# RJ45_connector.net
KiCad netlist of a schematic drawn in EAGLE
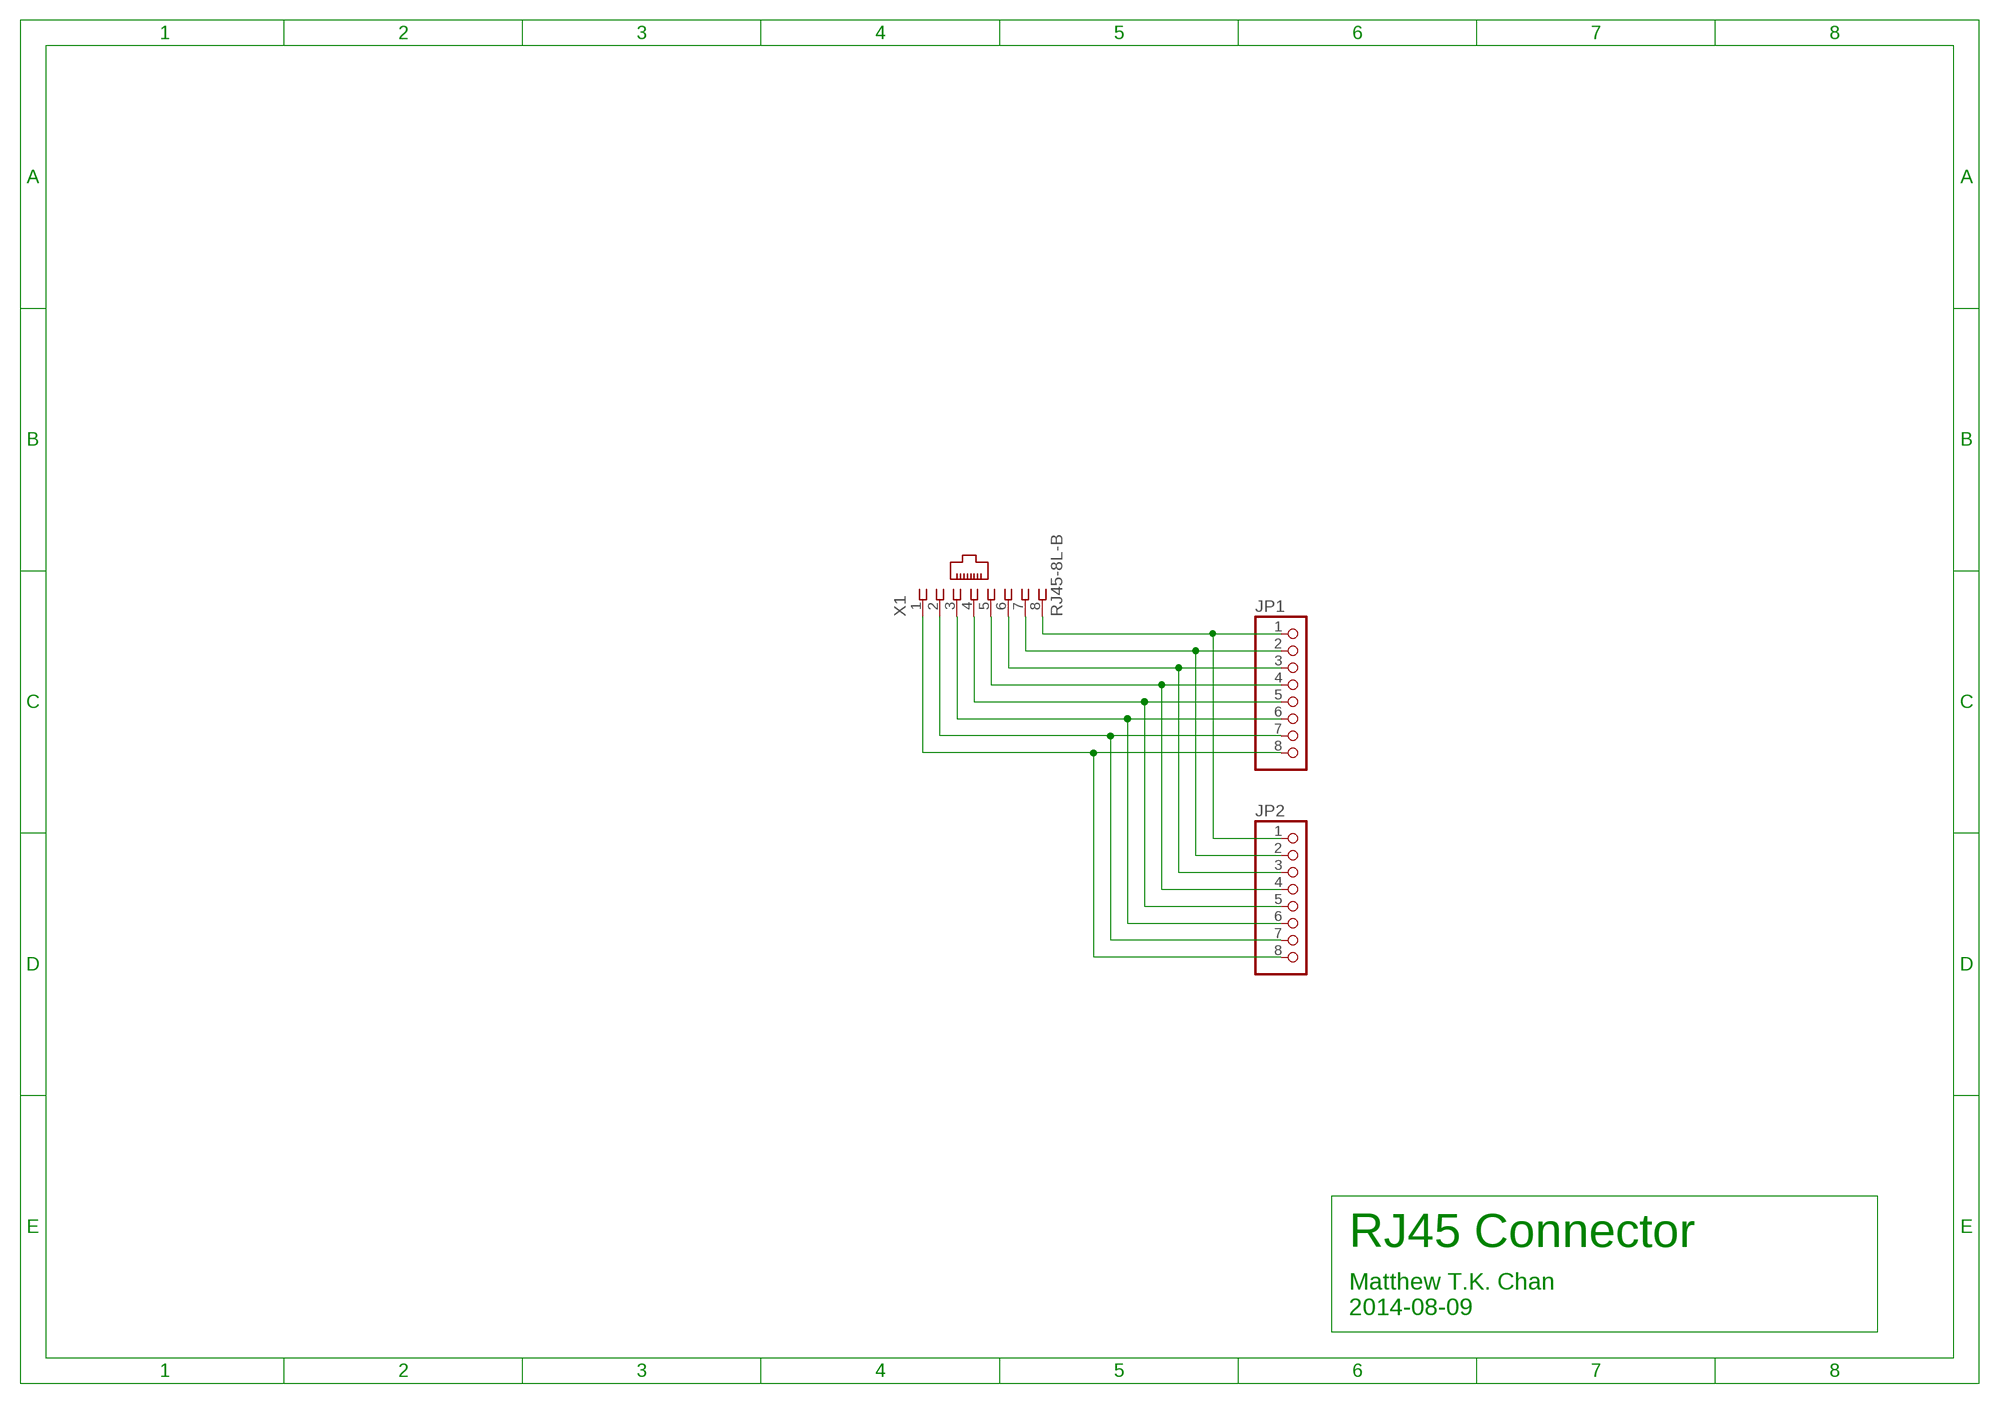
[diagram p0: schematic, sheet 1]

(export (version "E")
  (design (tool "Eeschema 10.0.6"))
  (components
    (comp (ref "JP1")
      (value "PINHD-1X8/90")
      (footprint "eagle-import:1X08_90")
      (libsource (lib "eagle-import") (part "PINHD-1X8/90"))
    )
    (comp (ref "JP2")
      (value "PINHD-1X8/90")
      (footprint "eagle-import:1X08_90")
      (libsource (lib "eagle-import") (part "PINHD-1X8/90"))
    )
    (comp (ref "X1")
      (value "RJ45-8L-B")
      (footprint "eagle-import:RJ45-NO-SHIELD")
      (fields (field (name "MF") "TYCO ELECTRONICS"))
      (libsource (lib "eagle-import") (part "RJ45-8L-B"))
    )
  )
  (nets
    (net (code "1") (name "Net-(JP1-Pad1)") (class "Default")
      (node (ref "JP1") (pin "1") (pinfunction "1_1") (pintype "passive"))
      (node (ref "JP2") (pin "1") (pinfunction "1_1") (pintype "passive"))
      (node (ref "X1") (pin "8") (pinfunction "8_8") (pintype "passive"))
    )
    (net (code "2") (name "Net-(JP1-Pad2)") (class "Default")
      (node (ref "JP1") (pin "2") (pinfunction "2_2") (pintype "passive"))
      (node (ref "JP2") (pin "2") (pinfunction "2_2") (pintype "passive"))
      (node (ref "X1") (pin "7") (pinfunction "7_7") (pintype "passive"))
    )
    (net (code "3") (name "Net-(JP1-Pad3)") (class "Default")
      (node (ref "JP1") (pin "3") (pinfunction "3_3") (pintype "passive"))
      (node (ref "JP2") (pin "3") (pinfunction "3_3") (pintype "passive"))
      (node (ref "X1") (pin "6") (pinfunction "6_6") (pintype "passive"))
    )
    (net (code "4") (name "Net-(JP1-Pad4)") (class "Default")
      (node (ref "JP1") (pin "4") (pinfunction "4_4") (pintype "passive"))
      (node (ref "JP2") (pin "4") (pinfunction "4_4") (pintype "passive"))
      (node (ref "X1") (pin "5") (pinfunction "5_5") (pintype "passive"))
    )
    (net (code "5") (name "Net-(JP1-Pad5)") (class "Default")
      (node (ref "JP1") (pin "5") (pinfunction "5_5") (pintype "passive"))
      (node (ref "JP2") (pin "5") (pinfunction "5_5") (pintype "passive"))
      (node (ref "X1") (pin "4") (pinfunction "4_4") (pintype "passive"))
    )
    (net (code "6") (name "Net-(JP1-Pad6)") (class "Default")
      (node (ref "JP1") (pin "6") (pinfunction "6_6") (pintype "passive"))
      (node (ref "JP2") (pin "6") (pinfunction "6_6") (pintype "passive"))
      (node (ref "X1") (pin "3") (pinfunction "3_3") (pintype "passive"))
    )
    (net (code "7") (name "Net-(JP1-Pad7)") (class "Default")
      (node (ref "JP1") (pin "7") (pinfunction "7_7") (pintype "passive"))
      (node (ref "JP2") (pin "7") (pinfunction "7_7") (pintype "passive"))
      (node (ref "X1") (pin "2") (pinfunction "2_2") (pintype "passive"))
    )
    (net (code "8") (name "Net-(JP1-Pad8)") (class "Default")
      (node (ref "JP1") (pin "8") (pinfunction "8_8") (pintype "passive"))
      (node (ref "JP2") (pin "8") (pinfunction "8_8") (pintype "passive"))
      (node (ref "X1") (pin "1") (pinfunction "1_1") (pintype "passive"))
    )
  )
)
